# synchronous.net
KiCad netlist of a schematic drawn in Altium Designer
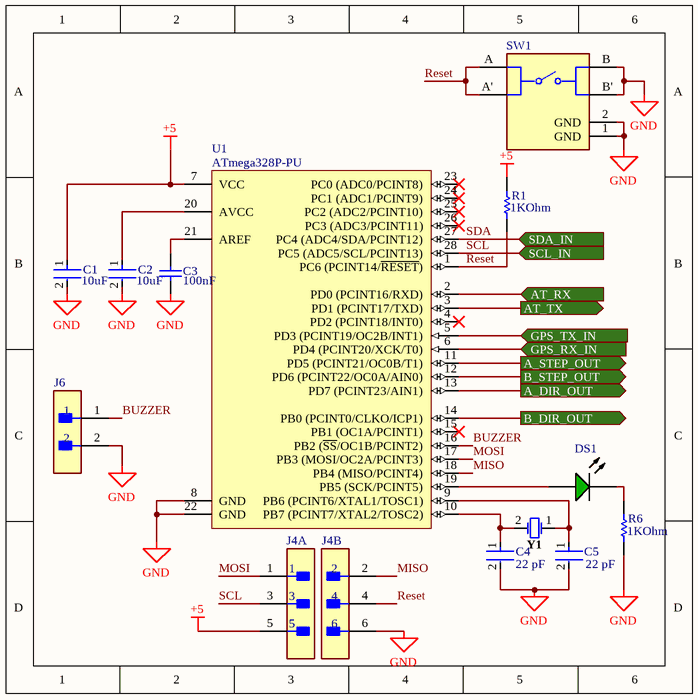
[diagram p0: synchronous.SchDoc]

(export (version "E")
  (design (tool "Eeschema 10.0.6"))
  (components
    (comp (ref "C1")
      (value "1206YD106KAT2A")
      (footprint "FP-1206-L_3_2_0_2-W_1_6_0-IPC_B")
      (description "General Purpose Ceramic Capacitor, 1206, 10uF, 10%, X5R, 15%, 16V")
      (fields
        (field (name "TOLERANCE") "10%")
        (field (name "CAPACITANCE") "10uF")
        (field (name "VOLTAGE") "16V")
      )
      (libsource (lib "Altium Content Vault") (part "02cd4be3c70576c341d710602a673aa"))
    )
    (comp (ref "C2")
      (value "1206YD106KAT2A")
      (footprint "FP-1206-L_3_2_0_2-W_1_6_0-IPC_B")
      (description "General Purpose Ceramic Capacitor, 1206, 10uF, 10%, X5R, 15%, 16V")
      (fields
        (field (name "TOLERANCE") "10%")
        (field (name "CAPACITANCE") "10uF")
        (field (name "VOLTAGE") "16V")
      )
      (libsource (lib "Altium Content Vault") (part "02cd4be3c70576c341d710602a673aa"))
    )
    (comp (ref "C3")
      (value "100nF")
      (footprint "CAPC2013X140X50LL20T25")
      (fields
        (field (name "MANUFACTURER") "AVX Interconnect / Elco")
        (field (name "PART NUMBER") "08055F104KAT2A")
      )
      (libsource (lib "Altium Content Vault") (part "CAP"))
    )
    (comp (ref "C4")
      (value "C0805C220K3GACTU")
      (footprint "FP-C0805C-DN-MFG")
      (description "CAP CER 22PF 25V 10% NP0 0805")
      (fields
        (field (name "TOLERANCE") "0.1")
        (field (name "OCTOPART") "https://octopart.com/c0805c220k3gactu-kemet-12580612")
        (field (name "CAPACITANCE") "22 pF")
      )
      (libsource (lib "Altium Content Vault") (part "b4654b650e69147ec39a6b967a45e02"))
    )
    (comp (ref "C5")
      (value "C0805C220K3GACTU")
      (footprint "FP-C0805C-DN-MFG")
      (description "CAP CER 22PF 25V 10% NP0 0805")
      (fields
        (field (name "TOLERANCE") "0.1")
        (field (name "OCTOPART") "https://octopart.com/c0805c220k3gactu-kemet-12580612")
        (field (name "CAPACITANCE") "22 pF")
      )
      (libsource (lib "Altium Content Vault") (part "b4654b650e69147ec39a6b967a45e02"))
    )
    (comp (ref "DS1")
      (value "HSMG-C170")
      (footprint "AVAG-HSMX-C170_V")
      (description "Chip LED, Green, 2.2 V, -40 to 85 degC, 2-Pin SMD, Pb-Free, Tape and Reel")
      (fields (field (name "MANUFACTURER") "Avago"))
      (libsource (lib "Altium Content Vault") (part "LED_GREEN_A1K2-2"))
    )
    (comp (ref "J4")
      (value "M20-9980346")
      (footprint "FP-M20-9980346-MFG")
      (description "CONN HEADER VERT 6POS 2.54MM")
      (fields
        (field (name "MANUFACTURER") "Harwin")
        (field (name "OCTOPART") "https://octopart.com/m20-9980346-harwin-5436545")
      )
      (libsource (lib "Altium Content Vault") (part "2654a11fb13586ecb194516b1c997bc"))
    )
    (comp (ref "J6")
      (value "B2B-XH-A(LF)(SN)")
      (footprint "FP-B2B-XH-A_LF_SN-MFG")
      (description "CONN HEADER VERT 2POS 2.5MM")
      (libsource (lib "Altium Content Vault") (part "3bc925449376181038e59eaffc5286c"))
    )
    (comp (ref "R1")
      (value "RC0805FR-071KL")
      (footprint "RESC2013X60X35ML10T20")
      (description "Chip Resistor, 1 KOhm, +/- 1%, 125 mW, -55 to 155 degC, 0805 (2012 Metric), RoHS, Tape and Reel")
      (fields
        (field (name "RESISTANCE") "1KOhm")
        (field (name "TOLERANCE") "1%")
        (field (name "MANUFACTURER") "Yageo")
      )
      (libsource (lib "Altium Content Vault") (part "RES-2"))
    )
    (comp (ref "R6")
      (value "RC0805FR-071KL")
      (footprint "RESC2013X60X35ML10T20")
      (description "Chip Resistor, 1 KOhm, +/- 1%, 125 mW, -55 to 155 degC, 0805 (2012 Metric), RoHS, Tape and Reel")
      (fields
        (field (name "RESISTANCE") "1KOhm")
        (field (name "TOLERANCE") "1%")
        (field (name "MANUFACTURER") "Yageo")
      )
      (libsource (lib "Altium Content Vault") (part "RES-2"))
    )
    (comp (ref "SW1")
      (value "EVQ-PLMA15")
      (footprint "FP-EVQ-PLMA15-MFG")
      (description "SWITCH TACTILE SPST-NO 0.02A 15V")
      (fields
        (field (name "OCTOPART") "https://octopart.com/evq-plma15-panasonic-39850235")
        (field (name "MANUFACTURER") "Panasonic Electronic Components")
      )
      (libsource (lib "Altium Content Vault") (part "fc7b47d2e4813f0909612a6c4f63938"))
    )
    (comp (ref "U1")
      (value "ATmega328P-PU")
      (footprint "28P3")
      (libsource (lib "Altium Content Vault") (part "MC-8B-ATM48-IL28"))
    )
    (comp (ref "Y1")
      (value "FOXSLF/160-20")
      (footprint "FOX-FOXSLF160-20")
      (description "Resistance Weld Thru-Hole Crystal, 16 MHz, -20 to 70 degC, 2-Pin THD, RoHS, Bulk")
      (fields (field (name "TOLERANCE") "1%"))
      (libsource (lib "Altium Content Vault") (part "XTAL-1-2-2"))
    )
  )
  (nets
    (net (code "1") (name "+5") (class "Default")
      (node (ref "C1") (pin "1") (pinfunction "1_1") (pintype "passive"))
      (node (ref "J4") (pin "5") (pinfunction "5_5") (pintype "passive"))
      (node (ref "R1") (pin "2") (pinfunction "2_2") (pintype "passive"))
      (node (ref "U1") (pin "7") (pinfunction "VCC_7") (pintype "power_in"))
    )
    (net (code "2") (name "/AT_RX") (class "Default")
      (node (ref "U1") (pin "2") (pinfunction "PD0_(PCINT16/RXD)_2") (pintype "bidirectional"))
    )
    (net (code "3") (name "/AT_TX") (class "Default")
      (node (ref "U1") (pin "3") (pinfunction "PD1_(PCINT17/TXD)_3") (pintype "bidirectional"))
    )
    (net (code "4") (name "/A_DIR_OUT") (class "Default")
      (node (ref "U1") (pin "13") (pinfunction "PD7_(PCINT23/AIN1)_13") (pintype "bidirectional"))
    )
    (net (code "5") (name "/A_STEP_OUT") (class "Default")
      (node (ref "U1") (pin "11") (pinfunction "PD5_(PCINT21/OC0B/T1)_11") (pintype "bidirectional"))
    )
    (net (code "6") (name "/BUZZER") (class "Default")
      (node (ref "J6") (pin "1") (pinfunction "1_1") (pintype "passive"))
      (node (ref "U1") (pin "16") (pinfunction "PB2_(~{SS}/OC1B/PCINT2)_16") (pintype "bidirectional"))
    )
    (net (code "7") (name "/B_DIR_OUT") (class "Default")
      (node (ref "U1") (pin "14") (pinfunction "PB0_(PCINT0/CLKO/ICP1)_14") (pintype "bidirectional"))
    )
    (net (code "8") (name "/B_STEP_OUT") (class "Default")
      (node (ref "U1") (pin "12") (pinfunction "PD6_(PCINT22/OC0A/AIN0)_12") (pintype "bidirectional"))
    )
    (net (code "9") (name "/GPS_RX_IN") (class "Default")
      (node (ref "U1") (pin "6") (pinfunction "PD4_(PCINT20/XCK/T0)_6") (pintype "input"))
    )
    (net (code "10") (name "/GPS_TX_IN") (class "Default")
      (node (ref "U1") (pin "5") (pinfunction "PD3_(PCINT19/OC2B/INT1)_5") (pintype "input"))
    )
    (net (code "11") (name "/MISO") (class "Default")
      (node (ref "J4") (pin "2") (pinfunction "2_2") (pintype "passive"))
      (node (ref "U1") (pin "18") (pinfunction "PB4_(MISO/PCINT4)_18") (pintype "bidirectional"))
    )
    (net (code "12") (name "/MOSI") (class "Default")
      (node (ref "J4") (pin "1") (pinfunction "1_1") (pintype "passive"))
      (node (ref "U1") (pin "17") (pinfunction "PB3_(MOSI/OC2A/PCINT3)_17") (pintype "bidirectional"))
    )
    (net (code "13") (name "/Reset") (class "Default")
      (node (ref "J4") (pin "4") (pinfunction "4_4") (pintype "passive"))
      (node (ref "R1") (pin "1") (pinfunction "1_1") (pintype "passive"))
      (node (ref "SW1") (pin "A") (pinfunction "A_A") (pintype "passive"))
      (node (ref "SW1") (pin "A'") (pinfunction "A'_A'") (pintype "passive"))
      (node (ref "U1") (pin "1") (pinfunction "PC6_(PCINT14/~{RESET})_1") (pintype "bidirectional"))
    )
    (net (code "14") (name "/SCL") (class "Default")
      (node (ref "J4") (pin "3") (pinfunction "3_3") (pintype "passive"))
      (node (ref "U1") (pin "28") (pinfunction "PC5_(ADC5/SCL/PCINT13)_28") (pintype "bidirectional"))
    )
    (net (code "16") (name "/SDA_IN") (class "Default")
      (node (ref "U1") (pin "27") (pinfunction "PC4_(ADC4/SDA/PCINT12)_27") (pintype "bidirectional"))
    )
    (net (code "17") (name "GND") (class "Default")
      (node (ref "C1") (pin "2") (pinfunction "2_2") (pintype "passive"))
      (node (ref "C2") (pin "2") (pinfunction "2_2") (pintype "passive"))
      (node (ref "C3") (pin "1") (pinfunction "1_1") (pintype "passive"))
      (node (ref "C4") (pin "2") (pinfunction "2_2") (pintype "passive"))
      (node (ref "C5") (pin "2") (pinfunction "2_2") (pintype "passive"))
      (node (ref "J4") (pin "6") (pinfunction "6_6") (pintype "passive"))
      (node (ref "J6") (pin "2") (pinfunction "2_2") (pintype "passive"))
      (node (ref "R6") (pin "1") (pinfunction "1_1") (pintype "passive"))
      (node (ref "SW1") (pin "1") (pinfunction "GND_1") (pintype "power_in"))
      (node (ref "SW1") (pin "2") (pinfunction "GND_2") (pintype "power_in"))
      (node (ref "SW1") (pin "B") (pinfunction "B_B") (pintype "passive"))
      (node (ref "SW1") (pin "B'") (pinfunction "B'_B'") (pintype "passive"))
      (node (ref "U1") (pin "22") (pinfunction "GND_22") (pintype "power_in"))
      (node (ref "U1") (pin "8") (pinfunction "GND_8") (pintype "power_in"))
    )
    (net (code "18") (name "Net-(DS1-A)") (class "Default")
      (node (ref "DS1") (pin "1") (pinfunction "A_1") (pintype "passive"))
      (node (ref "U1") (pin "19") (pinfunction "PB5_(SCK/PCINT5)_19") (pintype "bidirectional"))
    )
    (net (code "19") (name "Net-(DS1-K)") (class "Default")
      (node (ref "DS1") (pin "2") (pinfunction "K_2") (pintype "passive"))
      (node (ref "R6") (pin "2") (pinfunction "2_2") (pintype "passive"))
    )
    (net (code "20") (name "Net-(U1-AREF)") (class "Default")
      (node (ref "C3") (pin "2") (pinfunction "2_2") (pintype "passive"))
      (node (ref "U1") (pin "21") (pinfunction "AREF_21") (pintype "power_in"))
    )
    (net (code "21") (name "Net-(U1-AVCC)") (class "Default")
      (node (ref "C2") (pin "1") (pinfunction "1_1") (pintype "passive"))
      (node (ref "U1") (pin "20") (pinfunction "AVCC_20") (pintype "power_in"))
    )
    (net (code "22") (name "Net-(U1-PB6_(PCINT6{slash}XTAL1{slash}TOSC1))") (class "Default")
      (node (ref "C5") (pin "1") (pinfunction "1_1") (pintype "passive"))
      (node (ref "U1") (pin "9") (pinfunction "PB6_(PCINT6/XTAL1/TOSC1)_9") (pintype "bidirectional"))
      (node (ref "Y1") (pin "1") (pinfunction "1_1") (pintype "passive"))
    )
    (net (code "23") (name "Net-(U1-PB7_(PCINT7{slash}XTAL2{slash}TOSC2))") (class "Default")
      (node (ref "C4") (pin "1") (pinfunction "1_1") (pintype "passive"))
      (node (ref "U1") (pin "10") (pinfunction "PB7_(PCINT7/XTAL2/TOSC2)_10") (pintype "bidirectional"))
      (node (ref "Y1") (pin "2") (pinfunction "2_2") (pintype "passive"))
    )
    (net (code "24") (name "unconnected-(U1-PB1_(OC1A{slash}PCINT1)-Pad15)") (class "Default")
      (node (ref "U1") (pin "15") (pinfunction "PB1_(OC1A/PCINT1)_15") (pintype "bidirectional+no_connect"))
    )
    (net (code "25") (name "unconnected-(U1-PC0_(ADC0{slash}PCINT8)-Pad23)") (class "Default")
      (node (ref "U1") (pin "23") (pinfunction "PC0_(ADC0/PCINT8)_23") (pintype "bidirectional+no_connect"))
    )
    (net (code "26") (name "unconnected-(U1-PC1_(ADC1{slash}PCINT9)-Pad24)") (class "Default")
      (node (ref "U1") (pin "24") (pinfunction "PC1_(ADC1/PCINT9)_24") (pintype "bidirectional+no_connect"))
    )
    (net (code "27") (name "unconnected-(U1-PC2_(ADC2{slash}PCINT10)-Pad25)") (class "Default")
      (node (ref "U1") (pin "25") (pinfunction "PC2_(ADC2/PCINT10)_25") (pintype "bidirectional+no_connect"))
    )
    (net (code "28") (name "unconnected-(U1-PC3_(ADC3{slash}PCINT11)-Pad26)") (class "Default")
      (node (ref "U1") (pin "26") (pinfunction "PC3_(ADC3/PCINT11)_26") (pintype "bidirectional+no_connect"))
    )
    (net (code "29") (name "unconnected-(U1-PD2_(PCINT18{slash}INT0)-Pad4)") (class "Default")
      (node (ref "U1") (pin "4") (pinfunction "PD2_(PCINT18/INT0)_4") (pintype "bidirectional+no_connect"))
    )
  )
)
